# CD4093.net
KiCad netlist of a schematic drawn in Altium Designer
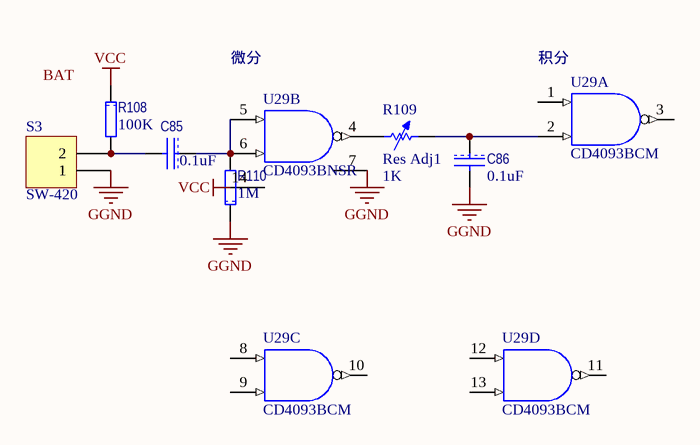
[diagram p0: CD4093.SchDoc]

(export (version "E")
  (design (tool "Eeschema 10.0.6"))
  (components
    (comp (ref "C85")
      (value "0.1uF")
      (footprint "1608[0603]C")
      (description "多层陶瓷电容器MLCC - SMD/SMT 0603 0.1uF 50volts X7R 10%")
      (fields (field (name "MANUFACTURER") "TDK") (field (name "MANUFACTURER PART NUMBER") "C1608X7R1H104K"))
      (libsource (lib "*") (part "CAP"))
    )
    (comp (ref "C86")
      (value "0.1uF")
      (footprint "1608[0603]C")
      (description "多层陶瓷电容器MLCC - SMD/SMT 0603 0.1uF 50volts X7R 10%")
      (fields (field (name "MANUFACTURER") "TDK") (field (name "MANUFACTURER PART NUMBER") "C1608X7R1H104K"))
      (libsource (lib "*") (part "CAP"))
    )
    (comp (ref "R108")
      (value "100K")
      (footprint "1608[0603]R")
      (description "厚膜电阻器 - SMD 1/10watt 100Kohms 1%")
      (fields
        (field (name "MANUFACTURER") "Vishay / Dale")
        (field (name "MANUFACTURER PART NUMBER") "CRCW0603100KFKEA")
      )
      (libsource (lib "100K 1%") (part "RES"))
    )
    (comp (ref "R109")
      (value "Res Adj1")
      (footprint "AXIAL-0.7")
      (description "Variable Resistor")
      (fields (field (name "ALTIUM_VALUE") "1K") (field (name "PUBLISHER") "Altium Limited"))
      (libsource (lib "Miscellaneous Devices") (part "Res Adj1"))
    )
    (comp (ref "R110")
      (value "1M")
      (footprint "1608[0603]R")
      (description "厚膜电阻器 - SMD 1/10watt 1.0Mohms 1%")
      (fields
        (field (name "MANUFACTURER") "Vishay / Dale")
        (field (name "MANUFACTURER PART NUMBER") "CRCW06031M00FKEA")
      )
      (libsource (lib "1M 1%") (part "RES"))
    )
    (comp (ref "S3")
      (value "SW-420")
      (footprint "AXIAL-0.5")
      (description "震动传感器")
      (fields (field (name "PUBLISHER") "Altium Limited"))
      (libsource (lib "Miscellaneous Connectors") (part "Header 2"))
    )
    (comp (ref "U29")
      (value "CD4093BCM")
      (footprint "M14A_N")
      (description "Quad 2-Input Schmitt-Trigger NAND Gate, 14-Pin SOIC")
      (fields (field (name "MANUFACTURER") "Texas Instruments") (field (name "PUBLISHER") "Altium Limited"))
      (libsource (lib "FSC Logic Gate") (part "CD4093BCM"))
    )
  )
  (nets
    (net (code "2") (name "GGND") (class "Default")
      (node (ref "C86") (pin "2") (pinfunction "2_2") (pintype "passive"))
      (node (ref "R110") (pin "1") (pinfunction "1_1") (pintype "passive"))
      (node (ref "S3") (pin "1") (pinfunction "1_1") (pintype "passive"))
      (node (ref "U29") (pin "7") (pinfunction "GND_7") (pintype "power_in"))
    )
    (net (code "3") (name "Net-(C85-Pad2)") (class "Default")
      (node (ref "C85") (pin "2") (pinfunction "2_2") (pintype "passive"))
      (node (ref "R108") (pin "2") (pinfunction "2_2") (pintype "passive"))
      (node (ref "S3") (pin "2") (pinfunction "2_2") (pintype "passive"))
    )
    (net (code "4") (name "Net-(U29A-B)") (class "Default")
      (node (ref "C86") (pin "1") (pinfunction "1_1") (pintype "passive"))
      (node (ref "R109") (pin "2") (pinfunction "2_2") (pintype "passive"))
      (node (ref "U29") (pin "2") (pinfunction "B_2") (pintype "input"))
    )
    (net (code "5") (name "Net-(U29B-C)") (class "Default")
      (node (ref "C85") (pin "1") (pinfunction "1_1") (pintype "passive"))
      (node (ref "R110") (pin "2") (pinfunction "2_2") (pintype "passive"))
      (node (ref "U29") (pin "5") (pinfunction "C_5") (pintype "input"))
      (node (ref "U29") (pin "6") (pinfunction "D_6") (pintype "input"))
    )
    (net (code "6") (name "Net-(U29B-K)") (class "Default")
      (node (ref "R109") (pin "1") (pinfunction "1_1") (pintype "passive"))
      (node (ref "U29") (pin "4") (pinfunction "K_4") (pintype "output"))
    )
    (net (code "7") (name "VCC") (class "Default")
      (node (ref "R108") (pin "1") (pinfunction "1_1") (pintype "passive"))
      (node (ref "U29") (pin "14") (pinfunction "VCC_14") (pintype "power_in"))
    )
    (net (code "8") (name "unconnected-(U29A-A-Pad1)") (class "Default")
      (node (ref "U29") (pin "1") (pinfunction "A_1") (pintype "input"))
    )
    (net (code "9") (name "unconnected-(U29A-J-Pad3)") (class "Default")
      (node (ref "U29") (pin "3") (pinfunction "J_3") (pintype "output"))
    )
    (net (code "10") (name "unconnected-(U29C-E-Pad8)") (class "Default")
      (node (ref "U29") (pin "8") (pinfunction "E_8") (pintype "input"))
    )
    (net (code "11") (name "unconnected-(U29C-F-Pad9)") (class "Default")
      (node (ref "U29") (pin "9") (pinfunction "F_9") (pintype "input"))
    )
    (net (code "12") (name "unconnected-(U29C-L-Pad10)") (class "Default")
      (node (ref "U29") (pin "10") (pinfunction "L_10") (pintype "output"))
    )
    (net (code "13") (name "unconnected-(U29D-G-Pad12)") (class "Default")
      (node (ref "U29") (pin "12") (pinfunction "G_12") (pintype "input"))
    )
    (net (code "14") (name "unconnected-(U29D-H-Pad13)") (class "Default")
      (node (ref "U29") (pin "13") (pinfunction "H_13") (pintype "input"))
    )
    (net (code "15") (name "unconnected-(U29D-M-Pad11)") (class "Default")
      (node (ref "U29") (pin "11") (pinfunction "M_11") (pintype "output"))
    )
  )
)
